# UART.net
KiCad netlist of a schematic drawn in Altium Designer
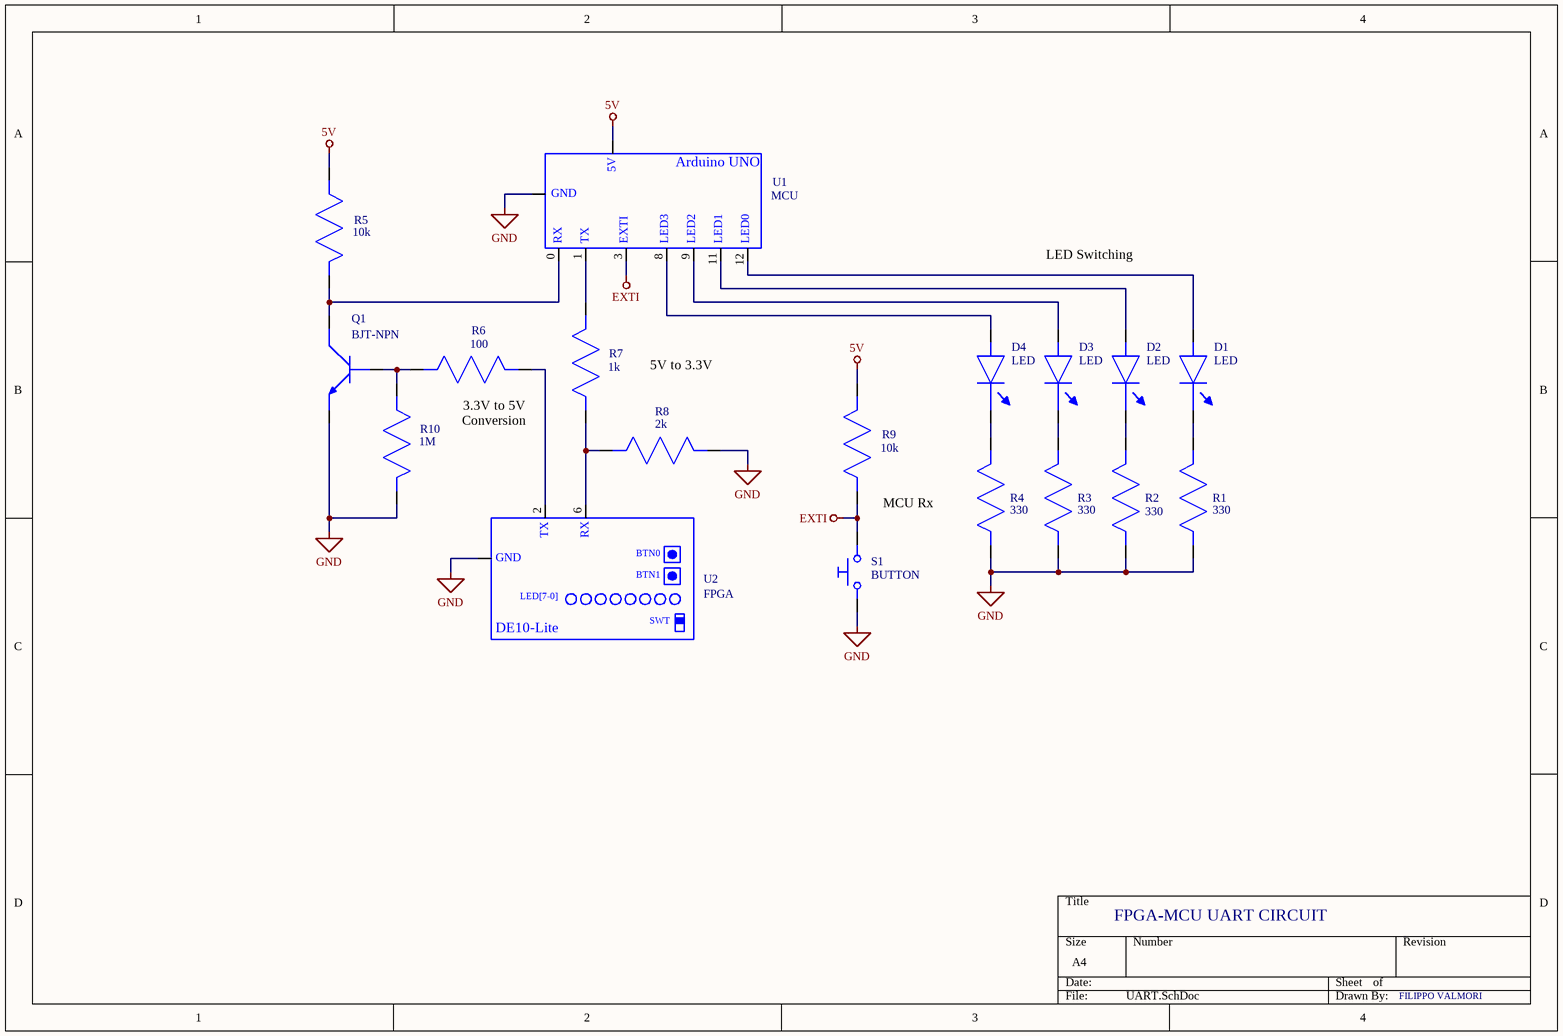
[diagram p0: UART.SchDoc]

(export (version "E")
  (design (tool "Eeschema 10.0.6"))
  (components
    (comp (ref "D1") (value "LED") (libsource (lib "UART") (part "LED")))
    (comp (ref "D2") (value "LED") (libsource (lib "UART") (part "LED")))
    (comp (ref "D3") (value "LED") (libsource (lib "UART") (part "LED")))
    (comp (ref "D4") (value "LED") (libsource (lib "UART") (part "LED")))
    (comp (ref "Q1") (value "BJT-NPN") (libsource (lib "UART") (part "BJT")))
    (comp (ref "R1") (value "330") (libsource (lib "UART") (part "RES330")))
    (comp (ref "R2") (value "330") (libsource (lib "UART") (part "RES330")))
    (comp (ref "R3") (value "330") (libsource (lib "UART") (part "RES330")))
    (comp (ref "R4") (value "330") (libsource (lib "UART") (part "RES330")))
    (comp (ref "R5") (value "10k") (libsource (lib "UART") (part "RES10K")))
    (comp (ref "R6") (value "100") (libsource (lib "UART") (part "RES100")))
    (comp (ref "R7") (value "1k") (libsource (lib "UART") (part "RES1K")))
    (comp (ref "R8") (value "2k") (libsource (lib "UART") (part "RES2K")))
    (comp (ref "R9") (value "10k") (libsource (lib "UART") (part "RES10K")))
    (comp (ref "R10") (value "1M") (libsource (lib "UART") (part "RES1M")))
    (comp (ref "S1") (value "BUTTON") (libsource (lib "UART") (part "BTN")))
    (comp (ref "U1") (value "MCU") (libsource (lib "UART") (part "MCU")))
    (comp (ref "U2") (value "FPGA") (libsource (lib "UART") (part "FPGA")))
  )
  (nets
    (net (code "1") (name "5V") (class "Default")
      (node (ref "R5") (pin "2") (pinfunction "2_2") (pintype "passive"))
      (node (ref "R9") (pin "2") (pinfunction "2_2") (pintype "passive"))
      (node (ref "U1") (pin "21") (pinfunction "21_21") (pintype "passive"))
    )
    (net (code "2") (name "EXTI") (class "Default")
      (node (ref "R9") (pin "1") (pinfunction "1_1") (pintype "passive"))
      (node (ref "S1") (pin "13") (pinfunction "13_13") (pintype "passive"))
      (node (ref "U1") (pin "3") (pinfunction "3_3") (pintype "passive"))
    )
    (net (code "3") (name "GND") (class "Default")
      (node (ref "Q1") (pin "3") (pinfunction "3_3") (pintype "passive"))
      (node (ref "R1") (pin "1") (pinfunction "1_1") (pintype "passive"))
      (node (ref "R10") (pin "1") (pinfunction "1_1") (pintype "passive"))
      (node (ref "R2") (pin "1") (pinfunction "1_1") (pintype "passive"))
      (node (ref "R3") (pin "1") (pinfunction "1_1") (pintype "passive"))
      (node (ref "R4") (pin "1") (pinfunction "1_1") (pintype "passive"))
      (node (ref "R8") (pin "2") (pinfunction "2_2") (pintype "passive"))
      (node (ref "S1") (pin "12") (pinfunction "12_12") (pintype "passive"))
      (node (ref "U1") (pin "16") (pinfunction "16_16") (pintype "passive"))
      (node (ref "U2") (pin "3") (pinfunction "3_3") (pintype "passive"))
    )
    (net (code "4") (name "Net-(D1-Pad1)") (class "Default")
      (node (ref "D1") (pin "1") (pinfunction "1_1") (pintype "passive"))
      (node (ref "U1") (pin "12") (pinfunction "12_12") (pintype "passive"))
    )
    (net (code "5") (name "Net-(D1-Pad2)") (class "Default")
      (node (ref "D1") (pin "2") (pinfunction "2_2") (pintype "passive"))
      (node (ref "R1") (pin "2") (pinfunction "2_2") (pintype "passive"))
    )
    (net (code "6") (name "Net-(D2-Pad1)") (class "Default")
      (node (ref "D2") (pin "1") (pinfunction "1_1") (pintype "passive"))
      (node (ref "U1") (pin "11") (pinfunction "11_11") (pintype "passive"))
    )
    (net (code "7") (name "Net-(D2-Pad2)") (class "Default")
      (node (ref "D2") (pin "2") (pinfunction "2_2") (pintype "passive"))
      (node (ref "R2") (pin "2") (pinfunction "2_2") (pintype "passive"))
    )
    (net (code "8") (name "Net-(D3-Pad1)") (class "Default")
      (node (ref "D3") (pin "1") (pinfunction "1_1") (pintype "passive"))
      (node (ref "U1") (pin "9") (pinfunction "9_9") (pintype "passive"))
    )
    (net (code "9") (name "Net-(D3-Pad2)") (class "Default")
      (node (ref "D3") (pin "2") (pinfunction "2_2") (pintype "passive"))
      (node (ref "R3") (pin "2") (pinfunction "2_2") (pintype "passive"))
    )
    (net (code "10") (name "Net-(D4-Pad1)") (class "Default")
      (node (ref "D4") (pin "1") (pinfunction "1_1") (pintype "passive"))
      (node (ref "U1") (pin "8") (pinfunction "8_8") (pintype "passive"))
    )
    (net (code "11") (name "Net-(D4-Pad2)") (class "Default")
      (node (ref "D4") (pin "2") (pinfunction "2_2") (pintype "passive"))
      (node (ref "R4") (pin "2") (pinfunction "2_2") (pintype "passive"))
    )
    (net (code "12") (name "Net-(Q1-Pad1)") (class "Default")
      (node (ref "Q1") (pin "1") (pinfunction "1_1") (pintype "passive"))
      (node (ref "R10") (pin "2") (pinfunction "2_2") (pintype "passive"))
      (node (ref "R6") (pin "2") (pinfunction "2_2") (pintype "passive"))
    )
    (net (code "13") (name "Net-(Q1-Pad2)") (class "Default")
      (node (ref "Q1") (pin "2") (pinfunction "2_2") (pintype "passive"))
      (node (ref "R5") (pin "1") (pinfunction "1_1") (pintype "passive"))
      (node (ref "U1") (pin "0") (pinfunction "0_0") (pintype "passive"))
    )
    (net (code "14") (name "Net-(R6-Pad1)") (class "Default")
      (node (ref "R6") (pin "1") (pinfunction "1_1") (pintype "passive"))
      (node (ref "U2") (pin "2") (pinfunction "2_2") (pintype "passive"))
    )
    (net (code "15") (name "Net-(R7-Pad1)") (class "Default")
      (node (ref "R7") (pin "1") (pinfunction "1_1") (pintype "passive"))
      (node (ref "R8") (pin "1") (pinfunction "1_1") (pintype "passive"))
      (node (ref "U2") (pin "6") (pinfunction "6_6") (pintype "passive"))
    )
    (net (code "16") (name "Net-(U1-15)") (class "Default")
      (node (ref "R7") (pin "2") (pinfunction "2_2") (pintype "passive"))
      (node (ref "U1") (pin "1") (pinfunction "15_1") (pintype "passive"))
    )
  )
)
